# XPDR_Board_2.net
KiCad netlist of a schematic drawn in EAGLE
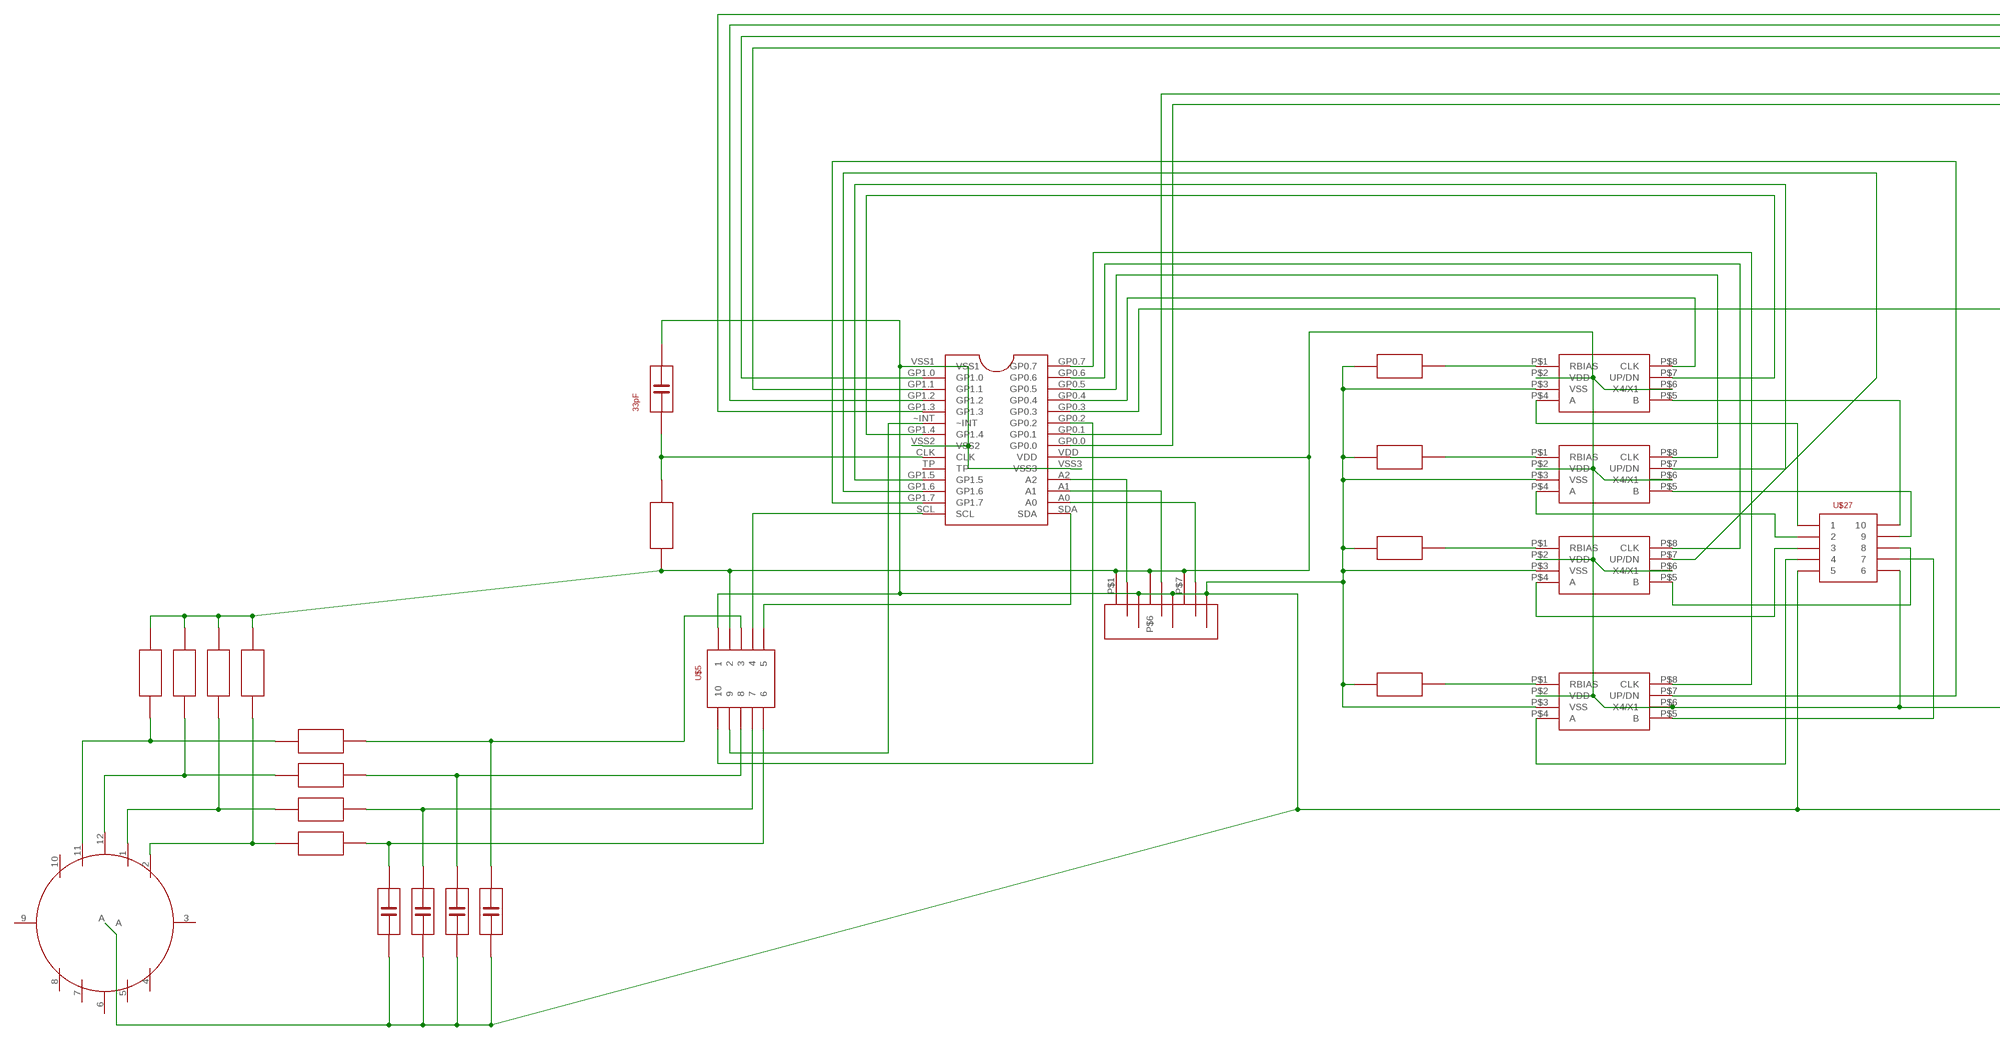
[diagram p0: schematic, sheet 1, part 1 of 2]
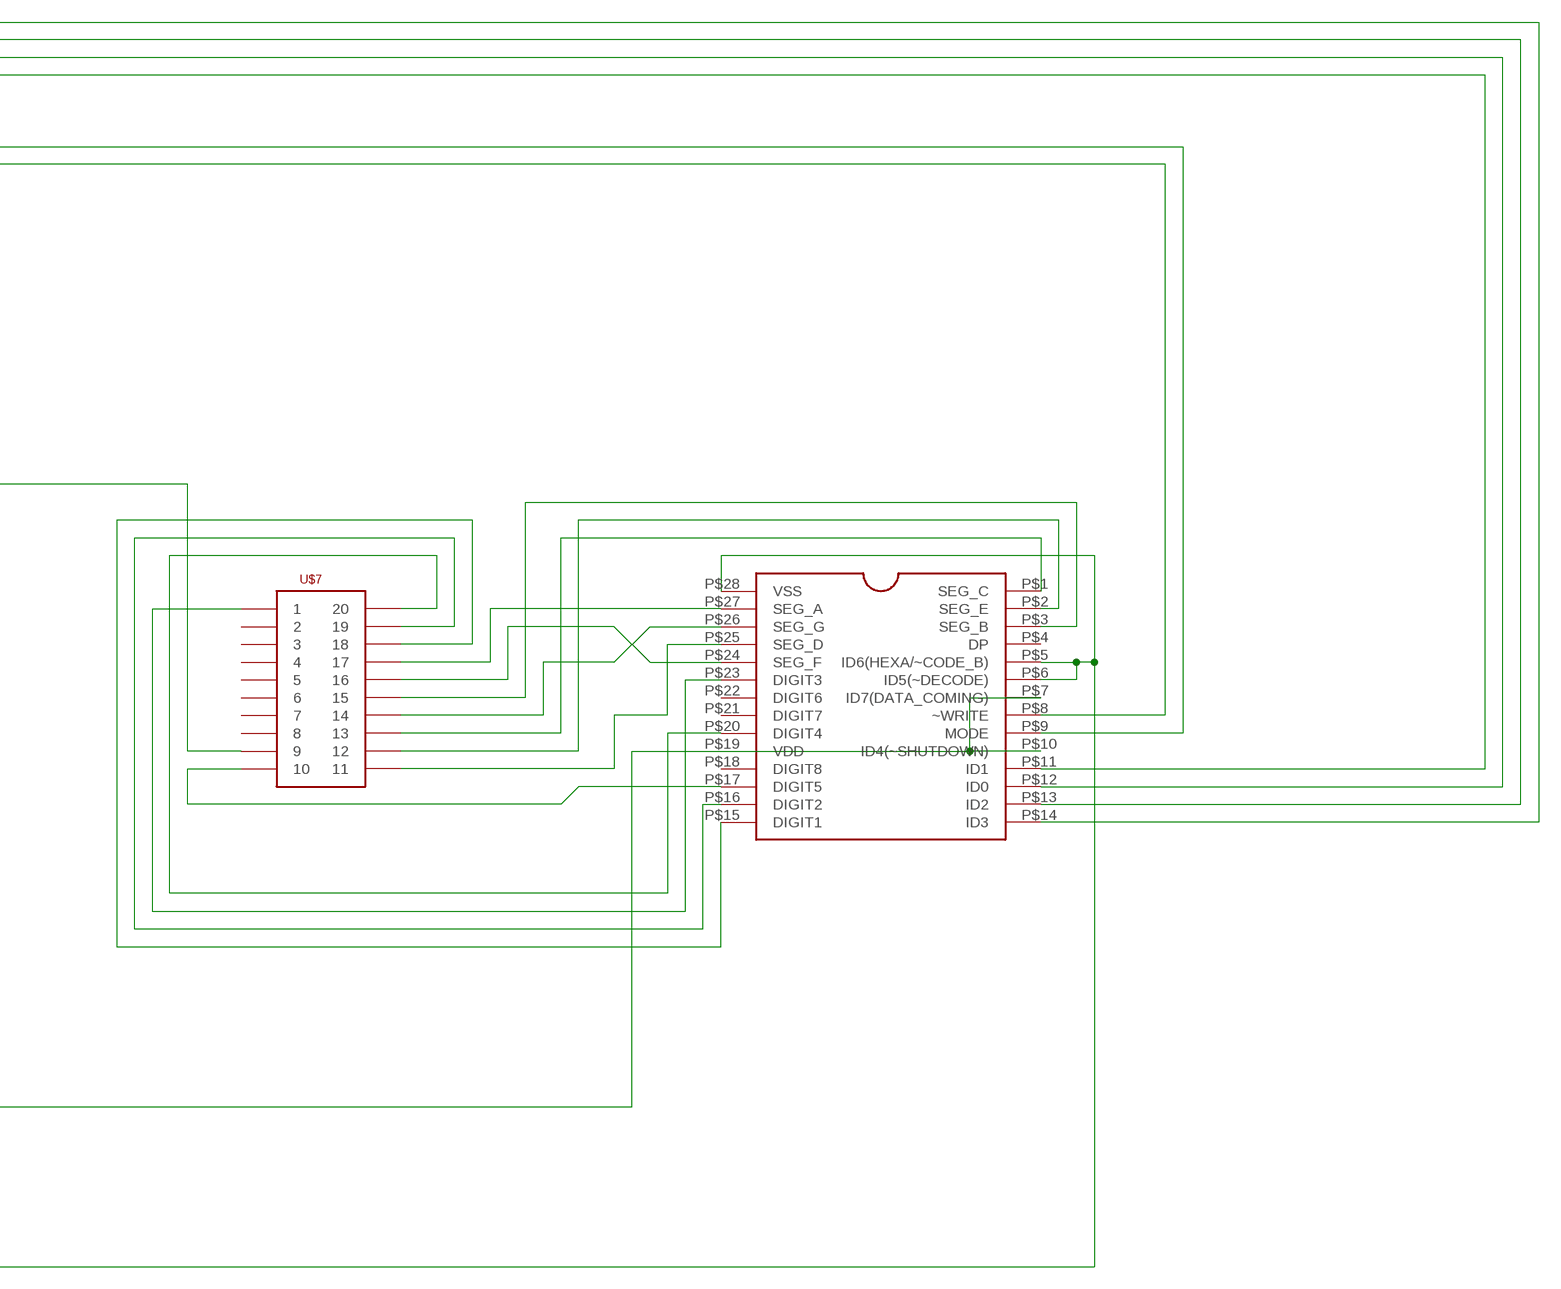
[diagram p1: schematic, sheet 1, part 2 of 2]

(export (version "E")
  (design (tool "Eeschema 10.0.6"))
  (components
    (comp (ref "U$1")
      (value "LS7084")
      (footprint "eagle-import:LS7084")
      (libsource (lib "eagle-import") (part "LS7084"))
    )
    (comp (ref "U$2")
      (value "LS7084")
      (footprint "eagle-import:LS7084")
      (libsource (lib "eagle-import") (part "LS7084"))
    )
    (comp (ref "U$3")
      (value "LS7084")
      (footprint "eagle-import:LS7084")
      (libsource (lib "eagle-import") (part "LS7084"))
    )
    (comp (ref "U$4")
      (value "LS7084")
      (footprint "eagle-import:LS7084")
      (libsource (lib "eagle-import") (part "LS7084"))
    )
    (comp (ref "U$5")
      (value "LISTA_2X5")
      (footprint "eagle-import:LISTA_2X5")
      (libsource (lib "eagle-import") (part "LISTA_2X5"))
    )
    (comp (ref "U$6")
      (value "ICM7228A")
      (footprint "eagle-import:ICM7228A")
      (libsource (lib "eagle-import") (part "ICM7228A"))
    )
    (comp (ref "U$7")
      (value "LISTA_2X10")
      (footprint "eagle-import:LISTA_2X10")
      (libsource (lib "eagle-import") (part "LISTA_2X10"))
    )
    (comp (ref "U$8")
      (value "470M")
      (footprint "eagle-import:REZISTOR")
      (libsource (lib "eagle-import") (part "REZISTOR"))
    )
    (comp (ref "U$9")
      (value "MCP23016")
      (footprint "eagle-import:MCP23016")
      (libsource (lib "eagle-import") (part "MCP23016"))
    )
    (comp (ref "U$10")
      (value "470M")
      (footprint "eagle-import:REZISTOR")
      (libsource (lib "eagle-import") (part "REZISTOR"))
    )
    (comp (ref "U$11")
      (value "ADRESA_0..2")
      (footprint "eagle-import:ADRESA_0..2")
      (libsource (lib "eagle-import") (part "ADRESA_0..2"))
    )
    (comp (ref "U$12")
      (value "470M")
      (footprint "eagle-import:REZISTOR")
      (libsource (lib "eagle-import") (part "REZISTOR"))
    )
    (comp (ref "U$13")
      (value "470M")
      (footprint "eagle-import:REZISTOR")
      (libsource (lib "eagle-import") (part "REZISTOR"))
    )
    (comp (ref "U$14")
      (value "3.9k")
      (footprint "eagle-import:REZISTOR")
      (libsource (lib "eagle-import") (part "REZISTOR"))
    )
    (comp (ref "U$15")
      (value "33pF")
      (footprint "eagle-import:KONDENZATOR")
      (libsource (lib "eagle-import") (part "KONDENZATOR"))
    )
    (comp (ref "U$16")
      (value "ROTARY_SWITCH")
      (footprint "eagle-import:ROTARY_SWITCH")
      (libsource (lib "eagle-import") (part "ROTARY_SWITCH"))
    )
    (comp (ref "U$17")
      (value "REZISTOR")
      (footprint "eagle-import:REZISTOR")
      (libsource (lib "eagle-import") (part "REZISTOR"))
    )
    (comp (ref "U$18")
      (value "REZISTOR")
      (footprint "eagle-import:REZISTOR")
      (libsource (lib "eagle-import") (part "REZISTOR"))
    )
    (comp (ref "U$19")
      (value "REZISTOR")
      (footprint "eagle-import:REZISTOR")
      (libsource (lib "eagle-import") (part "REZISTOR"))
    )
    (comp (ref "U$20")
      (value "REZISTOR")
      (footprint "eagle-import:REZISTOR")
      (libsource (lib "eagle-import") (part "REZISTOR"))
    )
    (comp (ref "U$21")
      (value "REZISTOR")
      (footprint "eagle-import:REZISTOR")
      (libsource (lib "eagle-import") (part "REZISTOR"))
    )
    (comp (ref "U$22")
      (value "REZISTOR")
      (footprint "eagle-import:REZISTOR")
      (libsource (lib "eagle-import") (part "REZISTOR"))
    )
    (comp (ref "U$23")
      (value "REZISTOR")
      (footprint "eagle-import:REZISTOR")
      (libsource (lib "eagle-import") (part "REZISTOR"))
    )
    (comp (ref "U$24")
      (value "REZISTOR")
      (footprint "eagle-import:REZISTOR")
      (libsource (lib "eagle-import") (part "REZISTOR"))
    )
    (comp (ref "U$25")
      (value "KONDENZATOR")
      (footprint "eagle-import:KONDENZATOR")
      (libsource (lib "eagle-import") (part "KONDENZATOR"))
    )
    (comp (ref "U$26")
      (value "KONDENZATOR")
      (footprint "eagle-import:KONDENZATOR")
      (libsource (lib "eagle-import") (part "KONDENZATOR"))
    )
    (comp (ref "U$27")
      (value "LISTA_2X5")
      (footprint "eagle-import:LISTA_2X5")
      (libsource (lib "eagle-import") (part "LISTA_2X5"))
    )
    (comp (ref "U$28")
      (value "KONDENZATOR")
      (footprint "eagle-import:KONDENZATOR")
      (libsource (lib "eagle-import") (part "KONDENZATOR"))
    )
    (comp (ref "U$29")
      (value "KONDENZATOR")
      (footprint "eagle-import:KONDENZATOR")
      (libsource (lib "eagle-import") (part "KONDENZATOR"))
    )
  )
  (nets
    (net (code "1") (name "Net-(U$1-A)") (class "Default")
      (node (ref "U$1") (pin "P$4") (pinfunction "A_P$4") (pintype "bidirectional"))
      (node (ref "U$27") (pin "1") (pinfunction "1_1") (pintype "bidirectional"))
    )
    (net (code "2") (name "Net-(U$1-B)") (class "Default")
      (node (ref "U$1") (pin "P$5") (pinfunction "B_P$5") (pintype "bidirectional"))
      (node (ref "U$27") (pin "10") (pinfunction "10_10") (pintype "bidirectional"))
    )
    (net (code "3") (name "Net-(U$1-CLK)") (class "Default")
      (node (ref "U$1") (pin "P$8") (pinfunction "CLK_P$8") (pintype "bidirectional"))
      (node (ref "U$9") (pin "GP0.4") (pinfunction "GP0.4_GP0.4") (pintype "bidirectional"))
    )
    (net (code "4") (name "Net-(U$1-RBIAS)") (class "Default")
      (node (ref "U$1") (pin "P$1") (pinfunction "RBIAS_P$1") (pintype "bidirectional"))
      (node (ref "U$8") (pin "P$2") (pinfunction "P$2_P$2") (pintype "bidirectional"))
    )
    (net (code "5") (name "Net-(U$1-UP{slash}DN)") (class "Default")
      (node (ref "U$1") (pin "P$7") (pinfunction "UP/DN_P$7") (pintype "bidirectional"))
      (node (ref "U$9") (pin "GP1.4") (pinfunction "GP1.4_GP1.4") (pintype "bidirectional"))
    )
    (net (code "6") (name "Net-(U$1-VDD)") (class "Default")
      (node (ref "U$1") (pin "P$2") (pinfunction "VDD_P$2") (pintype "bidirectional"))
      (node (ref "U$1") (pin "P$6") (pinfunction "X4/X1_P$6") (pintype "bidirectional"))
      (node (ref "U$11") (pin "P$1") (pinfunction "P$1_P$1") (pintype "bidirectional"))
      (node (ref "U$11") (pin "P$6") (pinfunction "P$6_P$6") (pintype "bidirectional"))
      (node (ref "U$11") (pin "P$7") (pinfunction "P$7_P$7") (pintype "bidirectional"))
      (node (ref "U$14") (pin "P$1") (pinfunction "P$1_P$1") (pintype "bidirectional"))
      (node (ref "U$17") (pin "P$1") (pinfunction "P$1_P$1") (pintype "bidirectional"))
      (node (ref "U$18") (pin "P$1") (pinfunction "P$1_P$1") (pintype "bidirectional"))
      (node (ref "U$19") (pin "P$1") (pinfunction "P$1_P$1") (pintype "bidirectional"))
      (node (ref "U$2") (pin "P$2") (pinfunction "VDD_P$2") (pintype "bidirectional"))
      (node (ref "U$2") (pin "P$6") (pinfunction "X4/X1_P$6") (pintype "bidirectional"))
      (node (ref "U$20") (pin "P$1") (pinfunction "P$1_P$1") (pintype "bidirectional"))
      (node (ref "U$27") (pin "6") (pinfunction "6_6") (pintype "bidirectional"))
      (node (ref "U$3") (pin "P$2") (pinfunction "VDD_P$2") (pintype "bidirectional"))
      (node (ref "U$3") (pin "P$6") (pinfunction "X4/X1_P$6") (pintype "bidirectional"))
      (node (ref "U$4") (pin "P$2") (pinfunction "VDD_P$2") (pintype "bidirectional"))
      (node (ref "U$4") (pin "P$6") (pinfunction "X4/X1_P$6") (pintype "bidirectional"))
      (node (ref "U$5") (pin "2") (pinfunction "2_2") (pintype "bidirectional"))
      (node (ref "U$6") (pin "P$10") (pinfunction "ID4(~{SHUTDOWN})_P$10") (pintype "bidirectional"))
      (node (ref "U$6") (pin "P$19") (pinfunction "VDD_P$19") (pintype "bidirectional"))
      (node (ref "U$6") (pin "P$7") (pinfunction "ID7(DATA_COMING)_P$7") (pintype "bidirectional"))
      (node (ref "U$9") (pin "VDD") (pinfunction "VDD_VDD") (pintype "bidirectional"))
    )
    (net (code "7") (name "Net-(U$1-VSS)") (class "Default")
      (node (ref "U$1") (pin "P$3") (pinfunction "VSS_P$3") (pintype "bidirectional"))
      (node (ref "U$10") (pin "P$1") (pinfunction "P$1_P$1") (pintype "bidirectional"))
      (node (ref "U$11") (pin "P$3") (pinfunction "P$3_P$3") (pintype "bidirectional"))
      (node (ref "U$11") (pin "P$4") (pinfunction "P$4_P$4") (pintype "bidirectional"))
      (node (ref "U$11") (pin "P$9") (pinfunction "P$9_P$9") (pintype "bidirectional"))
      (node (ref "U$12") (pin "P$1") (pinfunction "P$1_P$1") (pintype "bidirectional"))
      (node (ref "U$13") (pin "P$1") (pinfunction "P$1_P$1") (pintype "bidirectional"))
      (node (ref "U$15") (pin "P$2") (pinfunction "P$2_P$2") (pintype "bidirectional"))
      (node (ref "U$16") (pin "A") (pinfunction "A_A") (pintype "bidirectional"))
      (node (ref "U$2") (pin "P$3") (pinfunction "VSS_P$3") (pintype "bidirectional"))
      (node (ref "U$25") (pin "P$1") (pinfunction "P$1_P$1") (pintype "bidirectional"))
      (node (ref "U$26") (pin "P$1") (pinfunction "P$1_P$1") (pintype "bidirectional"))
      (node (ref "U$27") (pin "5") (pinfunction "5_5") (pintype "bidirectional"))
      (node (ref "U$28") (pin "P$1") (pinfunction "P$1_P$1") (pintype "bidirectional"))
      (node (ref "U$29") (pin "P$1") (pinfunction "P$1_P$1") (pintype "bidirectional"))
      (node (ref "U$3") (pin "P$3") (pinfunction "VSS_P$3") (pintype "bidirectional"))
      (node (ref "U$4") (pin "P$3") (pinfunction "VSS_P$3") (pintype "bidirectional"))
      (node (ref "U$5") (pin "1") (pinfunction "1_1") (pintype "bidirectional"))
      (node (ref "U$6") (pin "P$28") (pinfunction "VSS_P$28") (pintype "bidirectional"))
      (node (ref "U$6") (pin "P$5") (pinfunction "ID6(HEXA/~{CODE_B})_P$5") (pintype "bidirectional"))
      (node (ref "U$6") (pin "P$6") (pinfunction "ID5(~{DECODE})_P$6") (pintype "bidirectional"))
      (node (ref "U$8") (pin "P$1") (pinfunction "P$1_P$1") (pintype "bidirectional"))
      (node (ref "U$9") (pin "VSS1") (pinfunction "VSS1_VSS1") (pintype "bidirectional"))
      (node (ref "U$9") (pin "VSS2") (pinfunction "VSS2_VSS2") (pintype "bidirectional"))
      (node (ref "U$9") (pin "VSS3") (pinfunction "VSS3_VSS3") (pintype "bidirectional"))
    )
    (net (code "8") (name "Net-(U$2-A)") (class "Default")
      (node (ref "U$2") (pin "P$4") (pinfunction "A_P$4") (pintype "bidirectional"))
      (node (ref "U$27") (pin "2") (pinfunction "2_2") (pintype "bidirectional"))
    )
    (net (code "9") (name "Net-(U$2-B)") (class "Default")
      (node (ref "U$2") (pin "P$5") (pinfunction "B_P$5") (pintype "bidirectional"))
      (node (ref "U$27") (pin "9") (pinfunction "9_9") (pintype "bidirectional"))
    )
    (net (code "10") (name "Net-(U$2-CLK)") (class "Default")
      (node (ref "U$2") (pin "P$8") (pinfunction "CLK_P$8") (pintype "bidirectional"))
      (node (ref "U$9") (pin "GP0.5") (pinfunction "GP0.5_GP0.5") (pintype "bidirectional"))
    )
    (net (code "11") (name "Net-(U$2-RBIAS)") (class "Default")
      (node (ref "U$10") (pin "P$2") (pinfunction "P$2_P$2") (pintype "bidirectional"))
      (node (ref "U$2") (pin "P$1") (pinfunction "RBIAS_P$1") (pintype "bidirectional"))
    )
    (net (code "12") (name "Net-(U$2-UP{slash}DN)") (class "Default")
      (node (ref "U$2") (pin "P$7") (pinfunction "UP/DN_P$7") (pintype "bidirectional"))
      (node (ref "U$9") (pin "GP1.5") (pinfunction "GP1.5_GP1.5") (pintype "bidirectional"))
    )
    (net (code "13") (name "Net-(U$3-A)") (class "Default")
      (node (ref "U$27") (pin "3") (pinfunction "3_3") (pintype "bidirectional"))
      (node (ref "U$3") (pin "P$4") (pinfunction "A_P$4") (pintype "bidirectional"))
    )
    (net (code "14") (name "Net-(U$3-B)") (class "Default")
      (node (ref "U$27") (pin "8") (pinfunction "8_8") (pintype "bidirectional"))
      (node (ref "U$3") (pin "P$5") (pinfunction "B_P$5") (pintype "bidirectional"))
    )
    (net (code "15") (name "Net-(U$3-CLK)") (class "Default")
      (node (ref "U$3") (pin "P$8") (pinfunction "CLK_P$8") (pintype "bidirectional"))
      (node (ref "U$9") (pin "GP0.6") (pinfunction "GP0.6_GP0.6") (pintype "bidirectional"))
    )
    (net (code "16") (name "Net-(U$3-RBIAS)") (class "Default")
      (node (ref "U$12") (pin "P$2") (pinfunction "P$2_P$2") (pintype "bidirectional"))
      (node (ref "U$3") (pin "P$1") (pinfunction "RBIAS_P$1") (pintype "bidirectional"))
    )
    (net (code "17") (name "Net-(U$3-UP{slash}DN)") (class "Default")
      (node (ref "U$3") (pin "P$7") (pinfunction "UP/DN_P$7") (pintype "bidirectional"))
      (node (ref "U$9") (pin "GP1.6") (pinfunction "GP1.6_GP1.6") (pintype "bidirectional"))
    )
    (net (code "18") (name "Net-(U$4-A)") (class "Default")
      (node (ref "U$27") (pin "4") (pinfunction "4_4") (pintype "bidirectional"))
      (node (ref "U$4") (pin "P$4") (pinfunction "A_P$4") (pintype "bidirectional"))
    )
    (net (code "19") (name "Net-(U$4-B)") (class "Default")
      (node (ref "U$27") (pin "7") (pinfunction "7_7") (pintype "bidirectional"))
      (node (ref "U$4") (pin "P$5") (pinfunction "B_P$5") (pintype "bidirectional"))
    )
    (net (code "20") (name "Net-(U$4-CLK)") (class "Default")
      (node (ref "U$4") (pin "P$8") (pinfunction "CLK_P$8") (pintype "bidirectional"))
      (node (ref "U$9") (pin "GP0.7") (pinfunction "GP0.7_GP0.7") (pintype "bidirectional"))
    )
    (net (code "21") (name "Net-(U$4-RBIAS)") (class "Default")
      (node (ref "U$13") (pin "P$2") (pinfunction "P$2_P$2") (pintype "bidirectional"))
      (node (ref "U$4") (pin "P$1") (pinfunction "RBIAS_P$1") (pintype "bidirectional"))
    )
    (net (code "22") (name "Net-(U$4-UP{slash}DN)") (class "Default")
      (node (ref "U$4") (pin "P$7") (pinfunction "UP/DN_P$7") (pintype "bidirectional"))
      (node (ref "U$9") (pin "GP1.7") (pinfunction "GP1.7_GP1.7") (pintype "bidirectional"))
    )
    (net (code "23") (name "Net-(U$5-Pad4)") (class "Default")
      (node (ref "U$5") (pin "4") (pinfunction "4_4") (pintype "bidirectional"))
      (node (ref "U$9") (pin "SCL") (pinfunction "SCL_SCL") (pintype "bidirectional"))
    )
    (net (code "24") (name "Net-(U$5-Pad5)") (class "Default")
      (node (ref "U$5") (pin "5") (pinfunction "5_5") (pintype "bidirectional"))
      (node (ref "U$9") (pin "SDA") (pinfunction "SDA_SDA") (pintype "bidirectional"))
    )
    (net (code "25") (name "Net-(U$5-Pad10)") (class "Default")
      (node (ref "U$5") (pin "10") (pinfunction "10_10") (pintype "bidirectional"))
      (node (ref "U$9") (pin "GP0.2") (pinfunction "GP0.2_GP0.2") (pintype "bidirectional"))
    )
    (net (code "26") (name "Net-(U$6-DIGIT1)") (class "Default")
      (node (ref "U$6") (pin "P$15") (pinfunction "DIGIT1_P$15") (pintype "bidirectional"))
      (node (ref "U$7") (pin "18") (pinfunction "18_18") (pintype "bidirectional"))
    )
    (net (code "27") (name "Net-(U$6-DIGIT2)") (class "Default")
      (node (ref "U$6") (pin "P$16") (pinfunction "DIGIT2_P$16") (pintype "bidirectional"))
      (node (ref "U$7") (pin "19") (pinfunction "19_19") (pintype "bidirectional"))
    )
    (net (code "28") (name "Net-(U$6-DIGIT3)") (class "Default")
      (node (ref "U$6") (pin "P$23") (pinfunction "DIGIT3_P$23") (pintype "bidirectional"))
      (node (ref "U$7") (pin "1") (pinfunction "1_1") (pintype "bidirectional"))
    )
    (net (code "29") (name "Net-(U$6-DIGIT4)") (class "Default")
      (node (ref "U$6") (pin "P$20") (pinfunction "DIGIT4_P$20") (pintype "bidirectional"))
      (node (ref "U$7") (pin "20") (pinfunction "20_20") (pintype "bidirectional"))
    )
    (net (code "30") (name "Net-(U$6-DIGIT5)") (class "Default")
      (node (ref "U$6") (pin "P$17") (pinfunction "DIGIT5_P$17") (pintype "bidirectional"))
      (node (ref "U$7") (pin "10") (pinfunction "10_10") (pintype "bidirectional"))
    )
    (net (code "31") (name "Net-(U$6-ID0)") (class "Default")
      (node (ref "U$6") (pin "P$12") (pinfunction "ID0_P$12") (pintype "bidirectional"))
      (node (ref "U$9") (pin "GP1.0") (pinfunction "GP1.0_GP1.0") (pintype "bidirectional"))
    )
    (net (code "32") (name "Net-(U$6-ID1)") (class "Default")
      (node (ref "U$6") (pin "P$11") (pinfunction "ID1_P$11") (pintype "bidirectional"))
      (node (ref "U$9") (pin "GP1.1") (pinfunction "GP1.1_GP1.1") (pintype "bidirectional"))
    )
    (net (code "33") (name "Net-(U$6-ID2)") (class "Default")
      (node (ref "U$6") (pin "P$13") (pinfunction "ID2_P$13") (pintype "bidirectional"))
      (node (ref "U$9") (pin "GP1.2") (pinfunction "GP1.2_GP1.2") (pintype "bidirectional"))
    )
    (net (code "34") (name "Net-(U$6-ID3)") (class "Default")
      (node (ref "U$6") (pin "P$14") (pinfunction "ID3_P$14") (pintype "bidirectional"))
      (node (ref "U$9") (pin "GP1.3") (pinfunction "GP1.3_GP1.3") (pintype "bidirectional"))
    )
    (net (code "35") (name "Net-(U$6-MODE)") (class "Default")
      (node (ref "U$6") (pin "P$9") (pinfunction "MODE_P$9") (pintype "bidirectional"))
      (node (ref "U$9") (pin "GP0.1") (pinfunction "GP0.1_GP0.1") (pintype "bidirectional"))
    )
    (net (code "36") (name "Net-(U$6-SEG_A)") (class "Default")
      (node (ref "U$6") (pin "P$27") (pinfunction "SEG_A_P$27") (pintype "bidirectional"))
      (node (ref "U$7") (pin "17") (pinfunction "17_17") (pintype "bidirectional"))
    )
    (net (code "37") (name "Net-(U$6-SEG_B)") (class "Default")
      (node (ref "U$6") (pin "P$3") (pinfunction "SEG_B_P$3") (pintype "bidirectional"))
      (node (ref "U$7") (pin "15") (pinfunction "15_15") (pintype "bidirectional"))
    )
    (net (code "38") (name "Net-(U$6-SEG_C)") (class "Default")
      (node (ref "U$6") (pin "P$1") (pinfunction "SEG_C_P$1") (pintype "bidirectional"))
      (node (ref "U$7") (pin "13") (pinfunction "13_13") (pintype "bidirectional"))
    )
    (net (code "39") (name "Net-(U$6-SEG_D)") (class "Default")
      (node (ref "U$6") (pin "P$25") (pinfunction "SEG_D_P$25") (pintype "bidirectional"))
      (node (ref "U$7") (pin "11") (pinfunction "11_11") (pintype "bidirectional"))
    )
    (net (code "40") (name "Net-(U$6-SEG_E)") (class "Default")
      (node (ref "U$6") (pin "P$2") (pinfunction "SEG_E_P$2") (pintype "bidirectional"))
      (node (ref "U$7") (pin "12") (pinfunction "12_12") (pintype "bidirectional"))
    )
    (net (code "41") (name "Net-(U$6-SEG_F)") (class "Default")
      (node (ref "U$6") (pin "P$24") (pinfunction "SEG_F_P$24") (pintype "bidirectional"))
      (node (ref "U$7") (pin "16") (pinfunction "16_16") (pintype "bidirectional"))
    )
    (net (code "42") (name "Net-(U$6-SEG_G)") (class "Default")
      (node (ref "U$6") (pin "P$26") (pinfunction "SEG_G_P$26") (pintype "bidirectional"))
      (node (ref "U$7") (pin "14") (pinfunction "14_14") (pintype "bidirectional"))
    )
    (net (code "43") (name "Net-(U$6-~{WRITE})") (class "Default")
      (node (ref "U$6") (pin "P$8") (pinfunction "~{WRITE}_P$8") (pintype "bidirectional"))
      (node (ref "U$9") (pin "GP0.0") (pinfunction "GP0.0_GP0.0") (pintype "bidirectional"))
    )
    (net (code "44") (name "Net-(U$7-Pad9)") (class "Default")
      (node (ref "U$7") (pin "9") (pinfunction "9_9") (pintype "bidirectional"))
      (node (ref "U$9") (pin "GP0.3") (pinfunction "GP0.3_GP0.3") (pintype "bidirectional"))
    )
    (net (code "45") (name "Net-(U$9-~{INT})") (class "Default")
      (node (ref "U$5") (pin "9") (pinfunction "9_9") (pintype "bidirectional"))
      (node (ref "U$9") (pin "~INT") (pinfunction "~{INT}_~INT") (pintype "bidirectional"))
    )
    (net (code "46") (name "Net-(U$11-PadP$2)") (class "Default")
      (node (ref "U$11") (pin "P$2") (pinfunction "P$2_P$2") (pintype "bidirectional"))
      (node (ref "U$9") (pin "A2") (pinfunction "A2_A2") (pintype "bidirectional"))
    )
    (net (code "47") (name "Net-(U$11-PadP$5)") (class "Default")
      (node (ref "U$11") (pin "P$5") (pinfunction "P$5_P$5") (pintype "bidirectional"))
      (node (ref "U$9") (pin "A1") (pinfunction "A1_A1") (pintype "bidirectional"))
    )
    (net (code "48") (name "Net-(U$11-PadP$8)") (class "Default")
      (node (ref "U$11") (pin "P$8") (pinfunction "P$8_P$8") (pintype "bidirectional"))
      (node (ref "U$9") (pin "A0") (pinfunction "A0_A0") (pintype "bidirectional"))
    )
    (net (code "49") (name "Net-(U$14-PadP$2)") (class "Default")
      (node (ref "U$14") (pin "P$2") (pinfunction "P$2_P$2") (pintype "bidirectional"))
      (node (ref "U$15") (pin "P$1") (pinfunction "P$1_P$1") (pintype "bidirectional"))
      (node (ref "U$9") (pin "CLK") (pinfunction "CLK_CLK") (pintype "bidirectional"))
    )
    (net (code "50") (name "Net-(U$16-Pad1)") (class "Default")
      (node (ref "U$16") (pin "1") (pinfunction "1_1") (pintype "bidirectional"))
      (node (ref "U$19") (pin "P$2") (pinfunction "P$2_P$2") (pintype "bidirectional"))
      (node (ref "U$23") (pin "P$2") (pinfunction "P$2_P$2") (pintype "bidirectional"))
    )
    (net (code "51") (name "Net-(U$16-Pad2)") (class "Default")
      (node (ref "U$16") (pin "2") (pinfunction "2_2") (pintype "bidirectional"))
      (node (ref "U$20") (pin "P$2") (pinfunction "P$2_P$2") (pintype "bidirectional"))
      (node (ref "U$24") (pin "P$2") (pinfunction "P$2_P$2") (pintype "bidirectional"))
    )
    (net (code "52") (name "Net-(U$16-Pad11)") (class "Default")
      (node (ref "U$16") (pin "11") (pinfunction "11_11") (pintype "bidirectional"))
      (node (ref "U$17") (pin "P$2") (pinfunction "P$2_P$2") (pintype "bidirectional"))
      (node (ref "U$21") (pin "P$2") (pinfunction "P$2_P$2") (pintype "bidirectional"))
    )
    (net (code "53") (name "Net-(U$16-Pad12)") (class "Default")
      (node (ref "U$16") (pin "12") (pinfunction "12_12") (pintype "bidirectional"))
      (node (ref "U$18") (pin "P$2") (pinfunction "P$2_P$2") (pintype "bidirectional"))
      (node (ref "U$22") (pin "P$2") (pinfunction "P$2_P$2") (pintype "bidirectional"))
    )
    (net (code "54") (name "Net-(U$21-PadP$1)") (class "Default")
      (node (ref "U$21") (pin "P$1") (pinfunction "P$1_P$1") (pintype "bidirectional"))
      (node (ref "U$29") (pin "P$2") (pinfunction "P$2_P$2") (pintype "bidirectional"))
      (node (ref "U$5") (pin "3") (pinfunction "3_3") (pintype "bidirectional"))
    )
    (net (code "55") (name "Net-(U$22-PadP$1)") (class "Default")
      (node (ref "U$22") (pin "P$1") (pinfunction "P$1_P$1") (pintype "bidirectional"))
      (node (ref "U$28") (pin "P$2") (pinfunction "P$2_P$2") (pintype "bidirectional"))
      (node (ref "U$5") (pin "8") (pinfunction "8_8") (pintype "bidirectional"))
    )
    (net (code "56") (name "Net-(U$23-PadP$1)") (class "Default")
      (node (ref "U$23") (pin "P$1") (pinfunction "P$1_P$1") (pintype "bidirectional"))
      (node (ref "U$26") (pin "P$2") (pinfunction "P$2_P$2") (pintype "bidirectional"))
      (node (ref "U$5") (pin "7") (pinfunction "7_7") (pintype "bidirectional"))
    )
    (net (code "57") (name "Net-(U$24-PadP$1)") (class "Default")
      (node (ref "U$24") (pin "P$1") (pinfunction "P$1_P$1") (pintype "bidirectional"))
      (node (ref "U$25") (pin "P$2") (pinfunction "P$2_P$2") (pintype "bidirectional"))
      (node (ref "U$5") (pin "6") (pinfunction "6_6") (pintype "bidirectional"))
    )
    (net (code "58") (name "unconnected-(U$6-DIGIT6-PadP$22)") (class "Default")
      (node (ref "U$6") (pin "P$22") (pinfunction "DIGIT6_P$22") (pintype "bidirectional"))
    )
    (net (code "59") (name "unconnected-(U$6-DIGIT7-PadP$21)") (class "Default")
      (node (ref "U$6") (pin "P$21") (pinfunction "DIGIT7_P$21") (pintype "bidirectional"))
    )
    (net (code "60") (name "unconnected-(U$6-DIGIT8-PadP$18)") (class "Default")
      (node (ref "U$6") (pin "P$18") (pinfunction "DIGIT8_P$18") (pintype "bidirectional"))
    )
    (net (code "61") (name "unconnected-(U$6-DP-PadP$4)") (class "Default")
      (node (ref "U$6") (pin "P$4") (pinfunction "DP_P$4") (pintype "bidirectional"))
    )
    (net (code "62") (name "unconnected-(U$7-Pad2)") (class "Default")
      (node (ref "U$7") (pin "2") (pinfunction "2_2") (pintype "bidirectional"))
    )
    (net (code "63") (name "unconnected-(U$7-Pad3)") (class "Default")
      (node (ref "U$7") (pin "3") (pinfunction "3_3") (pintype "bidirectional"))
    )
    (net (code "64") (name "unconnected-(U$7-Pad4)") (class "Default")
      (node (ref "U$7") (pin "4") (pinfunction "4_4") (pintype "bidirectional"))
    )
    (net (code "65") (name "unconnected-(U$7-Pad5)") (class "Default")
      (node (ref "U$7") (pin "5") (pinfunction "5_5") (pintype "bidirectional"))
    )
    (net (code "66") (name "unconnected-(U$7-Pad6)") (class "Default")
      (node (ref "U$7") (pin "6") (pinfunction "6_6") (pintype "bidirectional"))
    )
    (net (code "67") (name "unconnected-(U$7-Pad7)") (class "Default")
      (node (ref "U$7") (pin "7") (pinfunction "7_7") (pintype "bidirectional"))
    )
    (net (code "68") (name "unconnected-(U$7-Pad8)") (class "Default")
      (node (ref "U$7") (pin "8") (pinfunction "8_8") (pintype "bidirectional"))
    )
    (net (code "69") (name "unconnected-(U$9-PadTP)") (class "Default")
      (node (ref "U$9") (pin "TP") (pinfunction "TP_TP") (pintype "bidirectional"))
    )
    (net (code "70") (name "unconnected-(U$16-Pad3)") (class "Default")
      (node (ref "U$16") (pin "3") (pinfunction "3_3") (pintype "bidirectional"))
    )
    (net (code "71") (name "unconnected-(U$16-Pad4)") (class "Default")
      (node (ref "U$16") (pin "4") (pinfunction "4_4") (pintype "bidirectional"))
    )
    (net (code "72") (name "unconnected-(U$16-Pad5)") (class "Default")
      (node (ref "U$16") (pin "5") (pinfunction "5_5") (pintype "bidirectional"))
    )
    (net (code "73") (name "unconnected-(U$16-Pad6)") (class "Default")
      (node (ref "U$16") (pin "6") (pinfunction "6_6") (pintype "bidirectional"))
    )
    (net (code "74") (name "unconnected-(U$16-Pad7)") (class "Default")
      (node (ref "U$16") (pin "7") (pinfunction "7_7") (pintype "bidirectional"))
    )
    (net (code "75") (name "unconnected-(U$16-Pad8)") (class "Default")
      (node (ref "U$16") (pin "8") (pinfunction "8_8") (pintype "bidirectional"))
    )
    (net (code "76") (name "unconnected-(U$16-Pad9)") (class "Default")
      (node (ref "U$16") (pin "9") (pinfunction "9_9") (pintype "bidirectional"))
    )
    (net (code "77") (name "unconnected-(U$16-Pad10)") (class "Default")
      (node (ref "U$16") (pin "10") (pinfunction "10_10") (pintype "bidirectional"))
    )
  )
)
